# PIC.net
KiCad netlist of a schematic drawn in Altium Designer
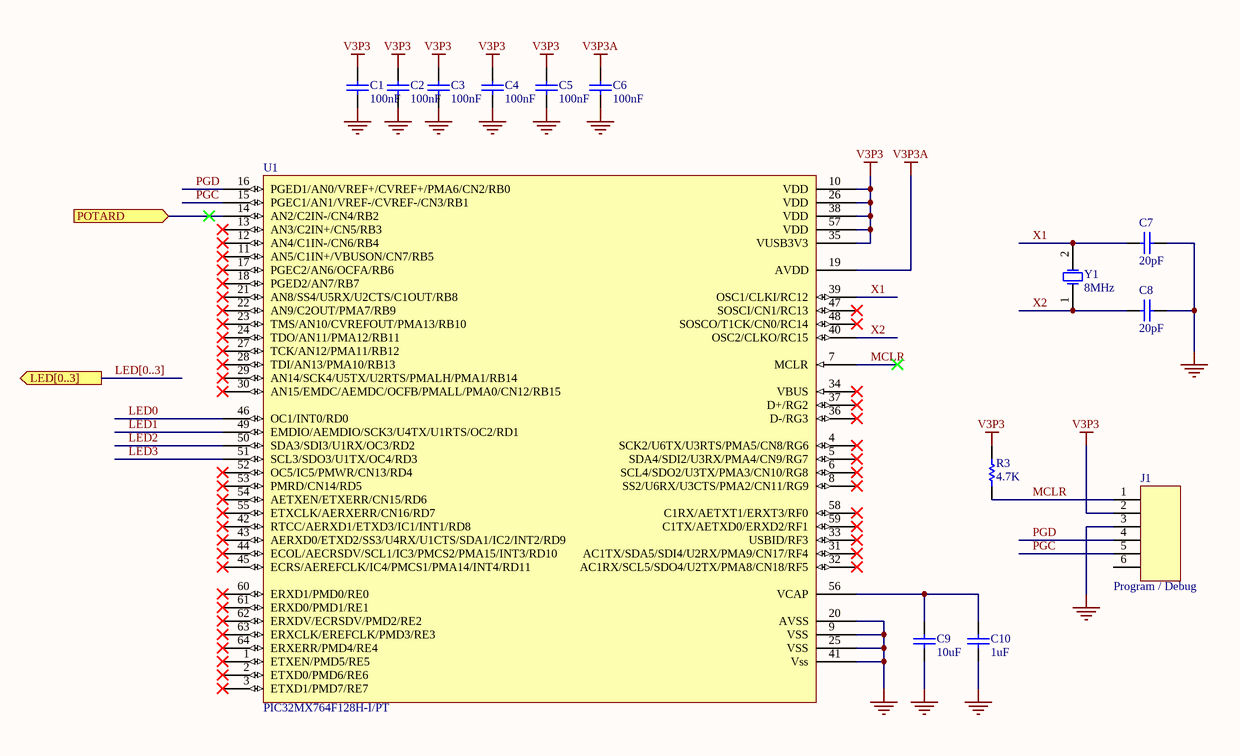
[diagram p0: PIC.SchDoc]

(export (version "E")
  (design (tool "Eeschema 10.0.6"))
  (components
    (comp (ref "C1")
      (value "100nF")
      (footprint "CAPC1608N")
      (description "Capacitor")
      (fields (field (name "PUBLISHER") "Altium Limited"))
      (libsource (lib "Miscellaneous Devices") (part "Cap"))
    )
    (comp (ref "C2")
      (value "100nF")
      (footprint "CAPC1608N")
      (description "Capacitor")
      (fields (field (name "PUBLISHER") "Altium Limited"))
      (libsource (lib "Miscellaneous Devices") (part "Cap"))
    )
    (comp (ref "C3")
      (value "100nF")
      (footprint "CAPC1608N")
      (description "Capacitor")
      (fields (field (name "PUBLISHER") "Altium Limited"))
      (libsource (lib "Miscellaneous Devices") (part "Cap"))
    )
    (comp (ref "C4")
      (value "100nF")
      (footprint "CAPC1608N")
      (description "Capacitor")
      (fields (field (name "PUBLISHER") "Altium Limited"))
      (libsource (lib "Miscellaneous Devices") (part "Cap"))
    )
    (comp (ref "C5")
      (value "100nF")
      (footprint "CAPC1608N")
      (description "Capacitor")
      (fields (field (name "PUBLISHER") "Altium Limited"))
      (libsource (lib "Miscellaneous Devices") (part "Cap"))
    )
    (comp (ref "C6")
      (value "100nF")
      (footprint "CAPC1608N")
      (description "Capacitor")
      (fields (field (name "PUBLISHER") "Altium Limited"))
      (libsource (lib "Miscellaneous Devices") (part "Cap"))
    )
    (comp (ref "C7")
      (value "20pF")
      (footprint "CAPC1608N")
      (description "Capacitor")
      (fields (field (name "PUBLISHER") "Altium Limited"))
      (libsource (lib "Miscellaneous Devices") (part "Cap"))
    )
    (comp (ref "C8")
      (value "20pF")
      (footprint "CAPC1608N")
      (description "Capacitor")
      (fields (field (name "PUBLISHER") "Altium Limited"))
      (libsource (lib "Miscellaneous Devices") (part "Cap"))
    )
    (comp (ref "C9")
      (value "10uF")
      (footprint "CAPC2012N")
      (description "Capacitor")
      (fields (field (name "PUBLISHER") "Altium Limited"))
      (libsource (lib "Miscellaneous Devices") (part "Cap"))
    )
    (comp (ref "C10")
      (value "1uF")
      (footprint "CAPC1608N")
      (description "Capacitor")
      (fields (field (name "PUBLISHER") "Altium Limited"))
      (libsource (lib "Miscellaneous Devices") (part "Cap"))
    )
    (comp (ref "J1")
      (value "Program / Debug")
      (footprint "RJ12_90")
      (description "Header, 6-Pin")
      (fields (field (name "PUBLISHER") "Altium Limited"))
      (libsource (lib "Miscellaneous Connectors") (part "Header 6"))
    )
    (comp (ref "R3")
      (value "4.7K")
      (footprint "RESC1608N")
      (description "Resistor")
      (fields (field (name "PUBLISHER") "Altium Limited"))
      (libsource (lib "Miscellaneous Devices") (part "Res1"))
    )
    (comp (ref "U1")
      (value "PIC32MX764F128H-I/PT")
      (footprint "QFP50P1200X1200X120-64")
      (libsource (lib "TP") (part "PIC32"))
    )
    (comp (ref "Y1")
      (value "8MHz")
      (footprint "HC49/4H SMX CRYSTAL")
      (description "Crystal Oscillator")
      (fields (field (name "PUBLISHER") "Altium Limited"))
      (libsource (lib "Miscellaneous Devices") (part "XTAL"))
    )
  )
  (nets
    (net (code "1") (name "/LED0") (class "Default")
      (node (ref "U1") (pin "46") (pinfunction "OC1/INT0/RD0_46") (pintype "bidirectional"))
    )
    (net (code "2") (name "/LED1") (class "Default")
      (node (ref "U1") (pin "49") (pinfunction "EMDIO/AEMDIO/SCK3/U4TX/U1RTS/OC2/RD1_49") (pintype "bidirectional"))
    )
    (net (code "3") (name "/LED2") (class "Default")
      (node (ref "U1") (pin "50") (pinfunction "SDA3/SDI3/U1RX/OC3/RD2_50") (pintype "bidirectional"))
    )
    (net (code "4") (name "/LED3") (class "Default")
      (node (ref "U1") (pin "51") (pinfunction "SCL3/SDO3/U1TX/OC4/RD3_51") (pintype "bidirectional"))
    )
    (net (code "6") (name "/MCLR") (class "Default")
      (node (ref "J1") (pin "1") (pinfunction "1_1") (pintype "passive"))
      (node (ref "R3") (pin "1") (pinfunction "1_1") (pintype "passive"))
      (node (ref "U1") (pin "7") (pinfunction "MCLR_7") (pintype "input"))
    )
    (net (code "7") (name "/PGC") (class "Default")
      (node (ref "J1") (pin "5") (pinfunction "5_5") (pintype "passive"))
      (node (ref "U1") (pin "15") (pinfunction "PGEC1/AN1/VREF-/CVREF-/CN3/RB1_15") (pintype "bidirectional"))
    )
    (net (code "8") (name "/PGD") (class "Default")
      (node (ref "J1") (pin "4") (pinfunction "4_4") (pintype "passive"))
      (node (ref "U1") (pin "16") (pinfunction "PGED1/AN0/VREF+/CVREF+/PMA6/CN2/RB0_16") (pintype "bidirectional"))
    )
    (net (code "9") (name "/POTARD") (class "Default")
      (node (ref "U1") (pin "14") (pinfunction "AN2/C2IN-/CN4/RB2_14") (pintype "bidirectional+no_connect"))
    )
    (net (code "10") (name "/X1") (class "Default")
      (node (ref "C7") (pin "2") (pinfunction "2_2") (pintype "passive"))
      (node (ref "U1") (pin "39") (pinfunction "OSC1/CLKI/RC12_39") (pintype "bidirectional"))
      (node (ref "Y1") (pin "2") (pinfunction "OSC2_2") (pintype "passive"))
    )
    (net (code "11") (name "/X2") (class "Default")
      (node (ref "C8") (pin "2") (pinfunction "2_2") (pintype "passive"))
      (node (ref "U1") (pin "40") (pinfunction "OSC2/CLKO/RC15_40") (pintype "bidirectional"))
      (node (ref "Y1") (pin "1") (pinfunction "OSC1_1") (pintype "passive"))
    )
    (net (code "12") (name "GND") (class "Default")
      (node (ref "C1") (pin "1") (pinfunction "1_1") (pintype "passive"))
      (node (ref "C10") (pin "1") (pinfunction "1_1") (pintype "passive"))
      (node (ref "C2") (pin "1") (pinfunction "1_1") (pintype "passive"))
      (node (ref "C3") (pin "1") (pinfunction "1_1") (pintype "passive"))
      (node (ref "C4") (pin "1") (pinfunction "1_1") (pintype "passive"))
      (node (ref "C5") (pin "1") (pinfunction "1_1") (pintype "passive"))
      (node (ref "C6") (pin "1") (pinfunction "1_1") (pintype "passive"))
      (node (ref "C7") (pin "1") (pinfunction "1_1") (pintype "passive"))
      (node (ref "C8") (pin "1") (pinfunction "1_1") (pintype "passive"))
      (node (ref "C9") (pin "1") (pinfunction "1_1") (pintype "passive"))
      (node (ref "J1") (pin "3") (pinfunction "3_3") (pintype "passive"))
      (node (ref "U1") (pin "20") (pinfunction "AVSS_20") (pintype "power_in"))
      (node (ref "U1") (pin "25") (pinfunction "VSS_25") (pintype "power_in"))
      (node (ref "U1") (pin "41") (pinfunction "Vss_41") (pintype "power_in"))
      (node (ref "U1") (pin "9") (pinfunction "VSS_9") (pintype "power_in"))
    )
    (net (code "13") (name "Net-(U1-VCAP)") (class "Default")
      (node (ref "C10") (pin "2") (pinfunction "2_2") (pintype "passive"))
      (node (ref "C9") (pin "2") (pinfunction "2_2") (pintype "passive"))
      (node (ref "U1") (pin "56") (pinfunction "VCAP_56") (pintype "power_in"))
    )
    (net (code "14") (name "V3P3") (class "Default")
      (node (ref "C1") (pin "2") (pinfunction "2_2") (pintype "passive"))
      (node (ref "C2") (pin "2") (pinfunction "2_2") (pintype "passive"))
      (node (ref "C3") (pin "2") (pinfunction "2_2") (pintype "passive"))
      (node (ref "C4") (pin "2") (pinfunction "2_2") (pintype "passive"))
      (node (ref "C5") (pin "2") (pinfunction "2_2") (pintype "passive"))
      (node (ref "J1") (pin "2") (pinfunction "2_2") (pintype "passive"))
      (node (ref "R3") (pin "2") (pinfunction "2_2") (pintype "passive"))
      (node (ref "U1") (pin "10") (pinfunction "VDD_10") (pintype "power_in"))
      (node (ref "U1") (pin "26") (pinfunction "VDD_26") (pintype "power_in"))
      (node (ref "U1") (pin "35") (pinfunction "VUSB3V3_35") (pintype "power_in"))
      (node (ref "U1") (pin "38") (pinfunction "VDD_38") (pintype "power_in"))
      (node (ref "U1") (pin "57") (pinfunction "VDD_57") (pintype "power_in"))
    )
    (net (code "15") (name "V3P3A") (class "Default")
      (node (ref "C6") (pin "2") (pinfunction "2_2") (pintype "passive"))
      (node (ref "U1") (pin "19") (pinfunction "AVDD_19") (pintype "power_in"))
    )
    (net (code "16") (name "unconnected-(J1-Pad6)") (class "Default")
      (node (ref "J1") (pin "6") (pinfunction "6_6") (pintype "passive"))
    )
    (net (code "17") (name "unconnected-(U1-AC1RX{slash}SCL5{slash}SDO4{slash}U2TX{slash}PMA8{slash}CN18{slash}RF5-Pad32)") (class "Default")
      (node (ref "U1") (pin "32") (pinfunction "AC1RX/SCL5/SDO4/U2TX/PMA8/CN18/RF5_32") (pintype "bidirectional+no_connect"))
    )
    (net (code "18") (name "unconnected-(U1-AC1TX{slash}SDA5{slash}SDI4{slash}U2RX{slash}PMA9{slash}CN17{slash}RF4-Pad31)") (class "Default")
      (node (ref "U1") (pin "31") (pinfunction "AC1TX/SDA5/SDI4/U2RX/PMA9/CN17/RF4_31") (pintype "bidirectional+no_connect"))
    )
    (net (code "19") (name "unconnected-(U1-AERXD0{slash}ETXD2{slash}SS3{slash}U4RX{slash}U1CTS{slash}SDA1{slash}IC2{slash}INT2{slash}RD9-Pad43)") (class "Default")
      (node (ref "U1") (pin "43") (pinfunction "AERXD0/ETXD2/SS3/U4RX/U1CTS/SDA1/IC2/INT2/RD9_43") (pintype "bidirectional+no_connect"))
    )
    (net (code "20") (name "unconnected-(U1-AETXEN{slash}ETXERR{slash}CN15{slash}RD6-Pad54)") (class "Default")
      (node (ref "U1") (pin "54") (pinfunction "AETXEN/ETXERR/CN15/RD6_54") (pintype "bidirectional+no_connect"))
    )
    (net (code "21") (name "unconnected-(U1-AN3{slash}C2IN+{slash}CN5{slash}RB3-Pad13)") (class "Default")
      (node (ref "U1") (pin "13") (pinfunction "AN3/C2IN+/CN5/RB3_13") (pintype "bidirectional+no_connect"))
    )
    (net (code "22") (name "unconnected-(U1-AN4{slash}C1IN-{slash}CN6{slash}RB4-Pad12)") (class "Default")
      (node (ref "U1") (pin "12") (pinfunction "AN4/C1IN-/CN6/RB4_12") (pintype "bidirectional+no_connect"))
    )
    (net (code "23") (name "unconnected-(U1-AN5{slash}C1IN+{slash}VBUSON{slash}CN7{slash}RB5-Pad11)") (class "Default")
      (node (ref "U1") (pin "11") (pinfunction "AN5/C1IN+/VBUSON/CN7/RB5_11") (pintype "bidirectional+no_connect"))
    )
    (net (code "24") (name "unconnected-(U1-AN8{slash}SS4{slash}U5RX{slash}U2CTS{slash}C1OUT{slash}RB8-Pad21)") (class "Default")
      (node (ref "U1") (pin "21") (pinfunction "AN8/SS4/U5RX/U2CTS/C1OUT/RB8_21") (pintype "bidirectional+no_connect"))
    )
    (net (code "25") (name "unconnected-(U1-AN9{slash}C2OUT{slash}PMA7{slash}RB9-Pad22)") (class "Default")
      (node (ref "U1") (pin "22") (pinfunction "AN9/C2OUT/PMA7/RB9_22") (pintype "bidirectional+no_connect"))
    )
    (net (code "26") (name "unconnected-(U1-AN14{slash}SCK4{slash}U5TX{slash}U2RTS{slash}PMALH{slash}PMA1{slash}RB14-Pad29)") (class "Default")
      (node (ref "U1") (pin "29") (pinfunction "AN14/SCK4/U5TX/U2RTS/PMALH/PMA1/RB14_29") (pintype "bidirectional+no_connect"))
    )
    (net (code "27") (name "unconnected-(U1-AN15{slash}EMDC{slash}AEMDC{slash}OCFB{slash}PMALL{slash}PMA0{slash}CN12{slash}RB15-Pad30)") (class "Default")
      (node (ref "U1") (pin "30") (pinfunction "AN15/EMDC/AEMDC/OCFB/PMALL/PMA0/CN12/RB15_30") (pintype "bidirectional+no_connect"))
    )
    (net (code "28") (name "unconnected-(U1-C1RX{slash}AETXT1{slash}ERXT3{slash}RF0-Pad58)") (class "Default")
      (node (ref "U1") (pin "58") (pinfunction "C1RX/AETXT1/ERXT3/RF0_58") (pintype "bidirectional+no_connect"))
    )
    (net (code "29") (name "unconnected-(U1-C1TX{slash}AETXD0{slash}ERXD2{slash}RF1-Pad59)") (class "Default")
      (node (ref "U1") (pin "59") (pinfunction "C1TX/AETXD0/ERXD2/RF1_59") (pintype "bidirectional+no_connect"))
    )
    (net (code "30") (name "unconnected-(U1-D+{slash}RG2-Pad37)") (class "Default")
      (node (ref "U1") (pin "37") (pinfunction "D+/RG2_37") (pintype "bidirectional+no_connect"))
    )
    (net (code "31") (name "unconnected-(U1-D-{slash}RG3-Pad36)") (class "Default")
      (node (ref "U1") (pin "36") (pinfunction "D-/RG3_36") (pintype "bidirectional+no_connect"))
    )
    (net (code "32") (name "unconnected-(U1-ECOL{slash}AECRSDV{slash}SCL1{slash}IC3{slash}PMCS2{slash}PMA15{slash}INT3{slash}RD10-Pad44)") (class "Default")
      (node (ref "U1") (pin "44") (pinfunction "ECOL/AECRSDV/SCL1/IC3/PMCS2/PMA15/INT3/RD10_44") (pintype "bidirectional+no_connect"))
    )
    (net (code "33") (name "unconnected-(U1-ECRS{slash}AEREFCLK{slash}IC4{slash}PMCS1{slash}PMA14{slash}INT4{slash}RD11-Pad45)") (class "Default")
      (node (ref "U1") (pin "45") (pinfunction "ECRS/AEREFCLK/IC4/PMCS1/PMA14/INT4/RD11_45") (pintype "bidirectional+no_connect"))
    )
    (net (code "34") (name "unconnected-(U1-ERXCLK{slash}EREFCLK{slash}PMD3{slash}RE3-Pad63)") (class "Default")
      (node (ref "U1") (pin "63") (pinfunction "ERXCLK/EREFCLK/PMD3/RE3_63") (pintype "bidirectional+no_connect"))
    )
    (net (code "35") (name "unconnected-(U1-ERXD0{slash}PMD1{slash}RE1-Pad61)") (class "Default")
      (node (ref "U1") (pin "61") (pinfunction "ERXD0/PMD1/RE1_61") (pintype "bidirectional+no_connect"))
    )
    (net (code "36") (name "unconnected-(U1-ERXD1{slash}PMD0{slash}RE0-Pad60)") (class "Default")
      (node (ref "U1") (pin "60") (pinfunction "ERXD1/PMD0/RE0_60") (pintype "bidirectional+no_connect"))
    )
    (net (code "37") (name "unconnected-(U1-ERXDV{slash}ECRSDV{slash}PMD2{slash}RE2-Pad62)") (class "Default")
      (node (ref "U1") (pin "62") (pinfunction "ERXDV/ECRSDV/PMD2/RE2_62") (pintype "bidirectional+no_connect"))
    )
    (net (code "38") (name "unconnected-(U1-ERXERR{slash}PMD4{slash}RE4-Pad64)") (class "Default")
      (node (ref "U1") (pin "64") (pinfunction "ERXERR/PMD4/RE4_64") (pintype "bidirectional+no_connect"))
    )
    (net (code "39") (name "unconnected-(U1-ETXCLK{slash}AERXERR{slash}CN16{slash}RD7-Pad55)") (class "Default")
      (node (ref "U1") (pin "55") (pinfunction "ETXCLK/AERXERR/CN16/RD7_55") (pintype "bidirectional+no_connect"))
    )
    (net (code "40") (name "unconnected-(U1-ETXD0{slash}PMD6{slash}RE6-Pad2)") (class "Default")
      (node (ref "U1") (pin "2") (pinfunction "ETXD0/PMD6/RE6_2") (pintype "bidirectional+no_connect"))
    )
    (net (code "41") (name "unconnected-(U1-ETXD1{slash}PMD7{slash}RE7-Pad3)") (class "Default")
      (node (ref "U1") (pin "3") (pinfunction "ETXD1/PMD7/RE7_3") (pintype "bidirectional+no_connect"))
    )
    (net (code "42") (name "unconnected-(U1-ETXEN{slash}PMD5{slash}RE5-Pad1)") (class "Default")
      (node (ref "U1") (pin "1") (pinfunction "ETXEN/PMD5/RE5_1") (pintype "bidirectional+no_connect"))
    )
    (net (code "43") (name "unconnected-(U1-OC5{slash}IC5{slash}PMWR{slash}CN13{slash}RD4-Pad52)") (class "Default")
      (node (ref "U1") (pin "52") (pinfunction "OC5/IC5/PMWR/CN13/RD4_52") (pintype "bidirectional+no_connect"))
    )
    (net (code "44") (name "unconnected-(U1-PGEC2{slash}AN6{slash}OCFA{slash}RB6-Pad17)") (class "Default")
      (node (ref "U1") (pin "17") (pinfunction "PGEC2/AN6/OCFA/RB6_17") (pintype "bidirectional+no_connect"))
    )
    (net (code "45") (name "unconnected-(U1-PGED2{slash}AN7{slash}RB7-Pad18)") (class "Default")
      (node (ref "U1") (pin "18") (pinfunction "PGED2/AN7/RB7_18") (pintype "bidirectional+no_connect"))
    )
    (net (code "46") (name "unconnected-(U1-PMRD{slash}CN14{slash}RD5-Pad53)") (class "Default")
      (node (ref "U1") (pin "53") (pinfunction "PMRD/CN14/RD5_53") (pintype "bidirectional+no_connect"))
    )
    (net (code "47") (name "unconnected-(U1-RTCC{slash}AERXD1{slash}ETXD3{slash}IC1{slash}INT1{slash}RD8-Pad42)") (class "Default")
      (node (ref "U1") (pin "42") (pinfunction "RTCC/AERXD1/ETXD3/IC1/INT1/RD8_42") (pintype "bidirectional+no_connect"))
    )
    (net (code "48") (name "unconnected-(U1-SCK2{slash}U6TX{slash}U3RTS{slash}PMA5{slash}CN8{slash}RG6-Pad4)") (class "Default")
      (node (ref "U1") (pin "4") (pinfunction "SCK2/U6TX/U3RTS/PMA5/CN8/RG6_4") (pintype "bidirectional+no_connect"))
    )
    (net (code "49") (name "unconnected-(U1-SCL4{slash}SDO2{slash}U3TX{slash}PMA3{slash}CN10{slash}RG8-Pad6)") (class "Default")
      (node (ref "U1") (pin "6") (pinfunction "SCL4/SDO2/U3TX/PMA3/CN10/RG8_6") (pintype "bidirectional+no_connect"))
    )
    (net (code "50") (name "unconnected-(U1-SDA4{slash}SDI2{slash}U3RX{slash}PMA4{slash}CN9{slash}RG7-Pad5)") (class "Default")
      (node (ref "U1") (pin "5") (pinfunction "SDA4/SDI2/U3RX/PMA4/CN9/RG7_5") (pintype "bidirectional+no_connect"))
    )
    (net (code "51") (name "unconnected-(U1-SOSCI{slash}CN1{slash}RC13-Pad47)") (class "Default")
      (node (ref "U1") (pin "47") (pinfunction "SOSCI/CN1/RC13_47") (pintype "bidirectional+no_connect"))
    )
    (net (code "52") (name "unconnected-(U1-SOSCO{slash}T1CK{slash}CN0{slash}RC14-Pad48)") (class "Default")
      (node (ref "U1") (pin "48") (pinfunction "SOSCO/T1CK/CN0/RC14_48") (pintype "bidirectional+no_connect"))
    )
    (net (code "53") (name "unconnected-(U1-SS2{slash}U6RX{slash}U3CTS{slash}PMA2{slash}CN11{slash}RG9-Pad8)") (class "Default")
      (node (ref "U1") (pin "8") (pinfunction "SS2/U6RX/U3CTS/PMA2/CN11/RG9_8") (pintype "bidirectional+no_connect"))
    )
    (net (code "54") (name "unconnected-(U1-TCK{slash}AN12{slash}PMA11{slash}RB12-Pad27)") (class "Default")
      (node (ref "U1") (pin "27") (pinfunction "TCK/AN12/PMA11/RB12_27") (pintype "bidirectional+no_connect"))
    )
    (net (code "55") (name "unconnected-(U1-TDI{slash}AN13{slash}PMA10{slash}RB13-Pad28)") (class "Default")
      (node (ref "U1") (pin "28") (pinfunction "TDI/AN13/PMA10/RB13_28") (pintype "bidirectional+no_connect"))
    )
    (net (code "56") (name "unconnected-(U1-TDO{slash}AN11{slash}PMA12{slash}RB11-Pad24)") (class "Default")
      (node (ref "U1") (pin "24") (pinfunction "TDO/AN11/PMA12/RB11_24") (pintype "bidirectional+no_connect"))
    )
    (net (code "57") (name "unconnected-(U1-TMS{slash}AN10{slash}CVREFOUT{slash}PMA13{slash}RB10-Pad23)") (class "Default")
      (node (ref "U1") (pin "23") (pinfunction "TMS/AN10/CVREFOUT/PMA13/RB10_23") (pintype "bidirectional+no_connect"))
    )
    (net (code "58") (name "unconnected-(U1-USBID{slash}RF3-Pad33)") (class "Default")
      (node (ref "U1") (pin "33") (pinfunction "USBID/RF3_33") (pintype "bidirectional+no_connect"))
    )
    (net (code "59") (name "unconnected-(U1-VBUS-Pad34)") (class "Default")
      (node (ref "U1") (pin "34") (pinfunction "VBUS_34") (pintype "input+no_connect"))
    )
  )
)
